# FEU2.net
KiCad netlist of a schematic drawn in EAGLE
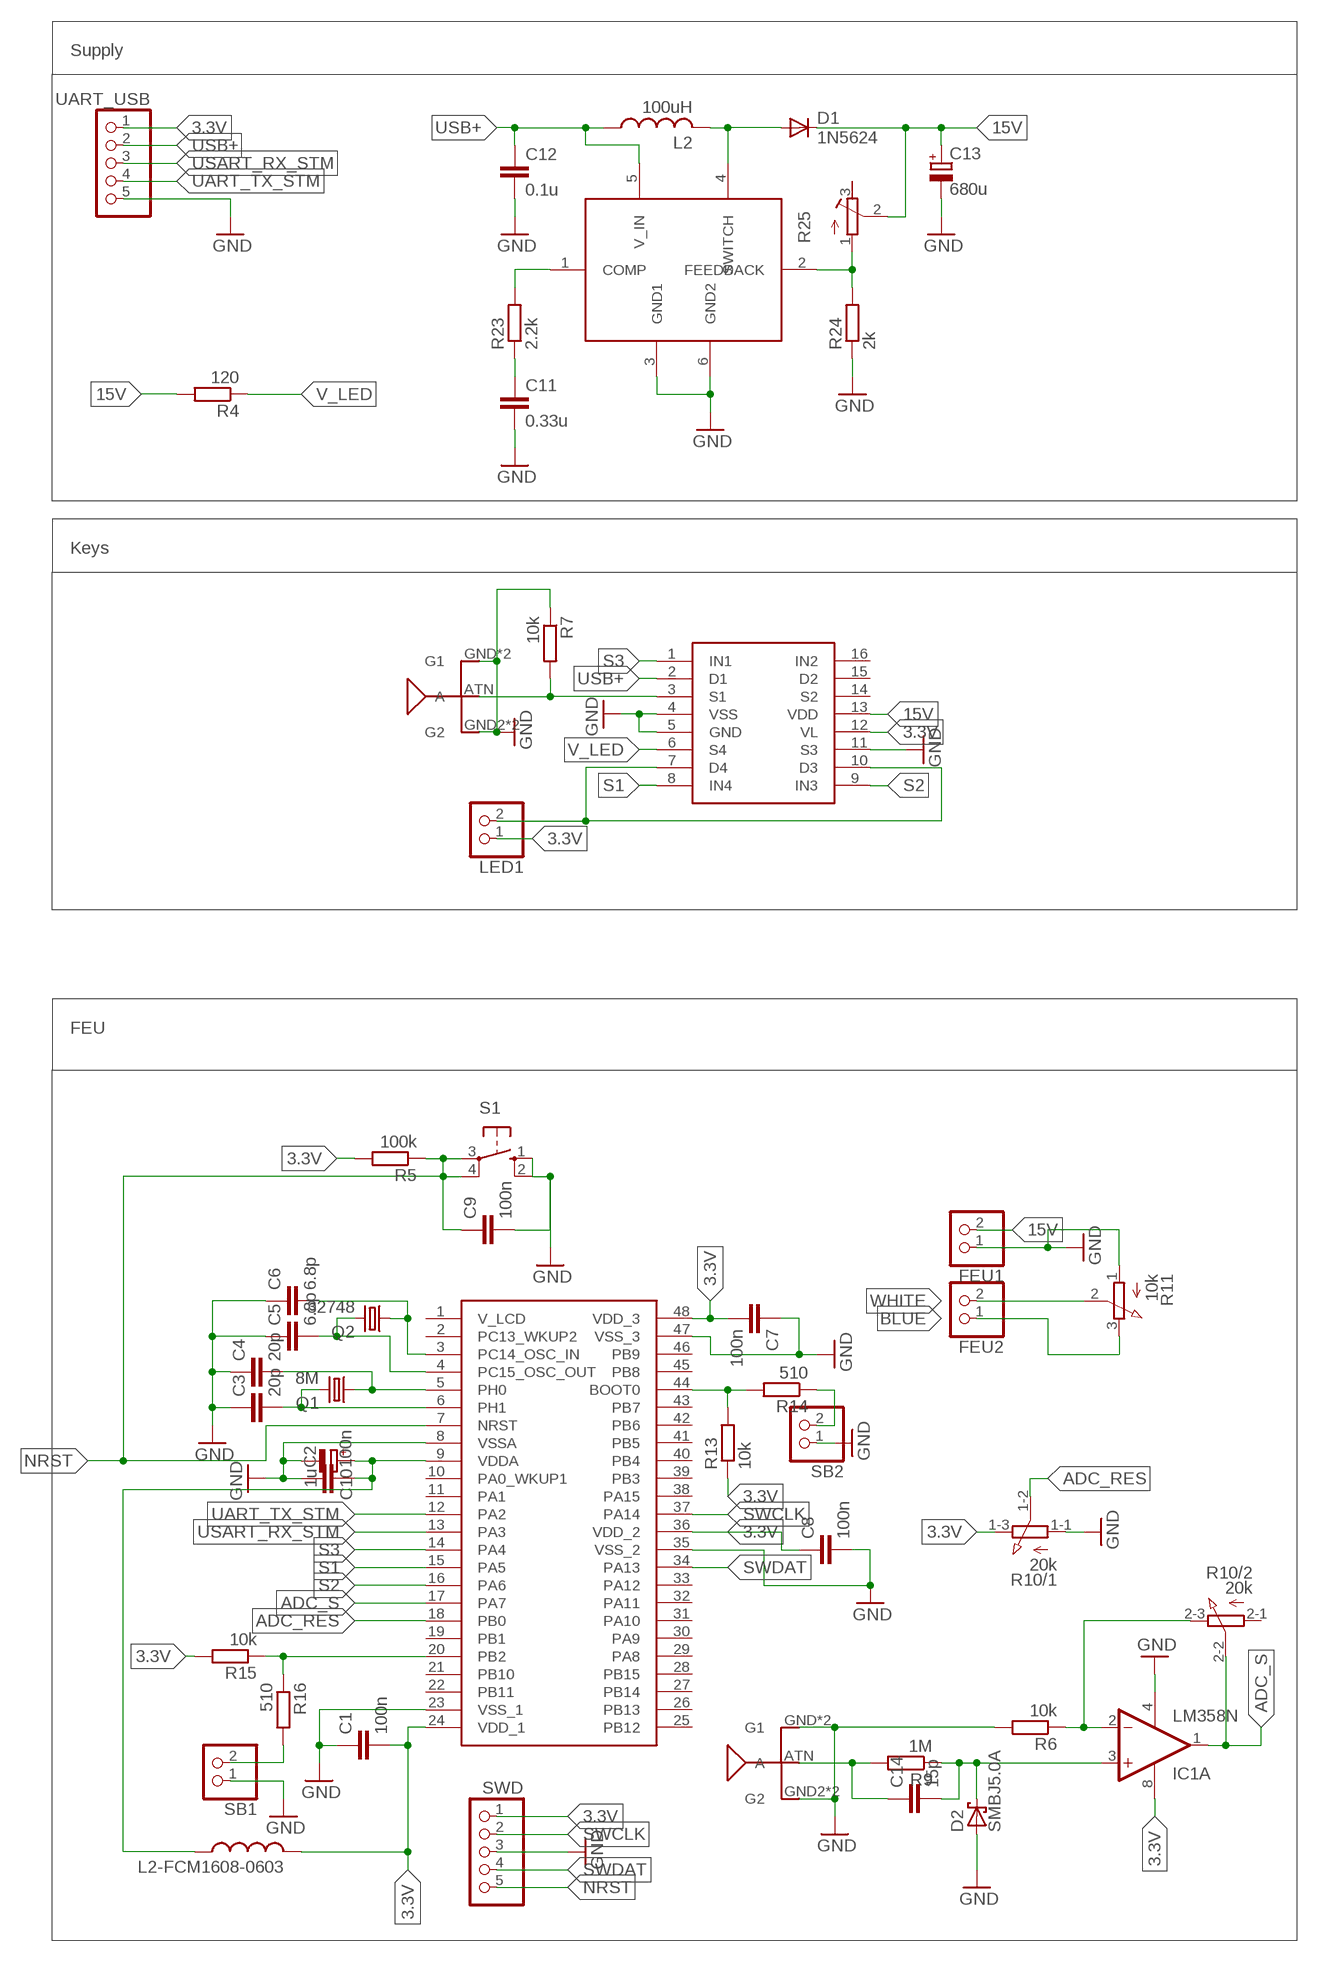
[diagram p0: schematic, sheet 1]

(export (version "E")
  (design (tool "Eeschema 10.0.6"))
  (components
    (comp (ref "C1")
      (value "100n")
      (footprint "eagle-import:C0805")
      (libsource (lib "eagle-import") (part "C-EUC0805"))
    )
    (comp (ref "C2")
      (value "100n")
      (footprint "eagle-import:C0805")
      (libsource (lib "eagle-import") (part "C-EUC0805"))
    )
    (comp (ref "C3")
      (value "20p")
      (footprint "eagle-import:C0805")
      (libsource (lib "eagle-import") (part "C-EUC0805"))
    )
    (comp (ref "C4")
      (value "20p")
      (footprint "eagle-import:C0805")
      (libsource (lib "eagle-import") (part "C-EUC0805"))
    )
    (comp (ref "C5")
      (value "6.8p")
      (footprint "eagle-import:C0805")
      (libsource (lib "eagle-import") (part "C-EUC0805"))
    )
    (comp (ref "C6")
      (value "6.8p")
      (footprint "eagle-import:C0805")
      (libsource (lib "eagle-import") (part "C-EUC0805"))
    )
    (comp (ref "C7")
      (value "100n")
      (footprint "eagle-import:C0805")
      (libsource (lib "eagle-import") (part "C-EUC0805"))
    )
    (comp (ref "C8")
      (value "100n")
      (footprint "eagle-import:C0805")
      (libsource (lib "eagle-import") (part "C-EUC0805"))
    )
    (comp (ref "C9")
      (value "100n")
      (footprint "eagle-import:C0805")
      (libsource (lib "eagle-import") (part "C-EUC0805"))
    )
    (comp (ref "C10")
      (value "1u")
      (footprint "eagle-import:A_3216-18W")
      (libsource (lib "eagle-import") (part "CPOL-EUA/3216-18W"))
    )
    (comp (ref "C11")
      (value "0.33u")
      (footprint "eagle-import:C0805")
      (libsource (lib "eagle-import") (part "C-EUC0805"))
    )
    (comp (ref "C12")
      (value "0.1u")
      (footprint "eagle-import:C0805")
      (libsource (lib "eagle-import") (part "C-EUC0805"))
    )
    (comp (ref "C13")
      (value "680u")
      (footprint "eagle-import:E5-5")
      (libsource (lib "eagle-import") (part "CPOL-EUE5-5"))
    )
    (comp (ref "C14")
      (value "15p")
      (footprint "eagle-import:C0805")
      (libsource (lib "eagle-import") (part "C-EUC0805"))
    )
    (comp (ref "D1")
      (value "1N5624")
      (footprint "eagle-import:DO201-15")
      (libsource (lib "eagle-import") (part "1N5624"))
    )
    (comp (ref "D2")
      (value "SMBJ5.0A")
      (footprint "eagle-import:C4111-15")
      (libsource (lib "eagle-import") (part "1N5908"))
    )
    (comp (ref "FEU1")
      (value "PINHD-1X2")
      (footprint "eagle-import:1X02")
      (libsource (lib "eagle-import") (part "PINHD-1X2"))
    )
    (comp (ref "FEU2")
      (value "PINHD-1X2")
      (footprint "eagle-import:1X02")
      (libsource (lib "eagle-import") (part "PINHD-1X2"))
    )
    (comp (ref "IC1")
      (value "LM358N")
      (footprint "eagle-import:DIL08")
      (libsource (lib "eagle-import") (part "LM358N"))
    )
    (comp (ref "L2")
      (value "100uH")
      (footprint "eagle-import:0207_5V")
      (libsource (lib "eagle-import") (part "L-US0207/5V"))
    )
    (comp (ref "L2-FCM1608-0603")
      (value "L-USL3216C")
      (footprint "eagle-import:L3216C")
      (libsource (lib "eagle-import") (part "L-USL3216C"))
    )
    (comp (ref "LED1")
      (value "PINHD-1X2")
      (footprint "eagle-import:1X02")
      (libsource (lib "eagle-import") (part "PINHD-1X2"))
    )
    (comp (ref "Q1")
      (value "8M")
      (footprint "eagle-import:HC49_S")
      (fields (field (name "OC_FARNELL") "1667008"))
      (libsource (lib "eagle-import") (part "CRYSTALHC49S"))
    )
    (comp (ref "Q2")
      (value "32748")
      (footprint "eagle-import:TC26H")
      (libsource (lib "eagle-import") (part "CRYSTALTC26H"))
    )
    (comp (ref "R4")
      (value "120")
      (footprint "eagle-import:R0805")
      (libsource (lib "eagle-import") (part "R-EU_R0805"))
    )
    (comp (ref "R5")
      (value "100k")
      (footprint "eagle-import:R0805")
      (libsource (lib "eagle-import") (part "R-EU_R0805"))
    )
    (comp (ref "R6")
      (value "10k")
      (footprint "eagle-import:M1206")
      (libsource (lib "eagle-import") (part "R-EU_M1206"))
    )
    (comp (ref "R7")
      (value "10k")
      (footprint "eagle-import:R0805")
      (libsource (lib "eagle-import") (part "R-EU_R0805"))
    )
    (comp (ref "R9")
      (value "1M")
      (footprint "eagle-import:M1206")
      (libsource (lib "eagle-import") (part "R-EU_M1206"))
    )
    (comp (ref "R10")
      (value "20k")
      (footprint "eagle-import:3RP_1610G")
      (libsource (lib "eagle-import") (part "3RP/1610G"))
    )
    (comp (ref "R11")
      (value "10k")
      (footprint "eagle-import:3RP_1610N")
      (libsource (lib "eagle-import") (part "3RP/1610N"))
    )
    (comp (ref "R13")
      (value "10k")
      (footprint "eagle-import:R0805")
      (libsource (lib "eagle-import") (part "R-EU_R0805"))
    )
    (comp (ref "R14")
      (value "510")
      (footprint "eagle-import:R0805")
      (libsource (lib "eagle-import") (part "R-EU_R0805"))
    )
    (comp (ref "R15")
      (value "10k")
      (footprint "eagle-import:R0805")
      (libsource (lib "eagle-import") (part "R-EU_R0805"))
    )
    (comp (ref "R16")
      (value "510")
      (footprint "eagle-import:R0805")
      (libsource (lib "eagle-import") (part "R-EU_R0805"))
    )
    (comp (ref "R23")
      (value "2.2k")
      (footprint "eagle-import:R0805")
      (libsource (lib "eagle-import") (part "R-EU_R0805"))
    )
    (comp (ref "R24")
      (value "2k")
      (footprint "eagle-import:R0805")
      (libsource (lib "eagle-import") (part "R-EU_R0805"))
    )
    (comp (ref "R25")
      (value "R-TRIMM3339P")
      (footprint "eagle-import:RTRIM3339P")
      (libsource (lib "eagle-import") (part "R-TRIMM3339P"))
    )
    (comp (ref "S1")
      (value "10-XX")
      (footprint "eagle-import:B3F-10XX")
      (fields (field (name "MPN") "B3F-1000"))
      (libsource (lib "eagle-import") (part "10-XX"))
    )
    (comp (ref "SB1")
      (value "PINHD-1X2")
      (footprint "eagle-import:1X02")
      (libsource (lib "eagle-import") (part "PINHD-1X2"))
    )
    (comp (ref "SB2")
      (value "PINHD-1X2")
      (footprint "eagle-import:1X02")
      (libsource (lib "eagle-import") (part "PINHD-1X2"))
    )
    (comp (ref "SWD")
      (value "PINHD-1X5")
      (footprint "eagle-import:1X05")
      (libsource (lib "eagle-import") (part "PINHD-1X5"))
    )
    (comp (ref "U$1")
      (value "STM32L152C6")
      (footprint "eagle-import:LQFP48")
      (libsource (lib "eagle-import") (part "STM32L152C6"))
    )
    (comp (ref "U$2")
      (value "GSM_ANT")
      (footprint "eagle-import:GSM")
      (libsource (lib "eagle-import") (part "GSM_ANT"))
    )
    (comp (ref "U$3")
      (value "GSM_ANT")
      (footprint "eagle-import:GSM")
      (libsource (lib "eagle-import") (part "GSM_ANT"))
    )
    (comp (ref "U$4")
      (value "LM2577")
      (footprint "eagle-import:TO263-5")
      (libsource (lib "eagle-import") (part "LM2577"))
    )
    (comp (ref "U$5")
      (value "ADG433BN")
      (footprint "eagle-import:DIL16")
      (libsource (lib "eagle-import") (part "ADG433BN"))
    )
    (comp (ref "UART_USB")
      (value "PINHD-1X5")
      (footprint "eagle-import:1X05")
      (libsource (lib "eagle-import") (part "PINHD-1X5"))
    )
  )
  (nets
    (net (code "1") (name "3.3V") (class "Default")
      (node (ref "C1") (pin "2") (pinfunction "2_2") (pintype "passive"))
      (node (ref "C7") (pin "2") (pinfunction "2_2") (pintype "passive"))
      (node (ref "C8") (pin "1") (pinfunction "1_1") (pintype "passive"))
      (node (ref "IC1") (pin "8") (pinfunction "V+_8") (pintype "power_in"))
      (node (ref "L2-FCM1608-0603") (pin "2") (pinfunction "2_2") (pintype "passive"))
      (node (ref "LED1") (pin "1") (pinfunction "1_1") (pintype "passive"))
      (node (ref "R10") (pin "1-3") (pinfunction "E_1-3") (pintype "passive"))
      (node (ref "R13") (pin "1") (pinfunction "1_1") (pintype "passive"))
      (node (ref "R15") (pin "2") (pinfunction "2_2") (pintype "passive"))
      (node (ref "R5") (pin "2") (pinfunction "2_2") (pintype "passive"))
      (node (ref "SWD") (pin "1") (pinfunction "1_1") (pintype "passive"))
      (node (ref "U$1") (pin "24") (pinfunction "VDD_1_24") (pintype "bidirectional"))
      (node (ref "U$1") (pin "36") (pinfunction "VDD_2_36") (pintype "bidirectional"))
      (node (ref "U$1") (pin "48") (pinfunction "VDD_3_48") (pintype "bidirectional"))
      (node (ref "U$5") (pin "12") (pinfunction "VL_12") (pintype "bidirectional"))
      (node (ref "UART_USB") (pin "1") (pinfunction "1_1") (pintype "passive"))
    )
    (net (code "2") (name "15V") (class "Default")
      (node (ref "C13") (pin "+") (pinfunction "+_+") (pintype "passive"))
      (node (ref "D1") (pin "C") (pinfunction "C_C") (pintype "passive"))
      (node (ref "FEU1") (pin "2") (pinfunction "2_2") (pintype "passive"))
      (node (ref "R25") (pin "2") (pinfunction "S_2") (pintype "passive"))
      (node (ref "R4") (pin "2") (pinfunction "2_2") (pintype "passive"))
      (node (ref "U$5") (pin "13") (pinfunction "VDD_13") (pintype "bidirectional"))
    )
    (net (code "3") (name "ADC_RES") (class "Default")
      (node (ref "R10") (pin "1-2") (pinfunction "S_1-2") (pintype "passive"))
      (node (ref "U$1") (pin "18") (pinfunction "PB0_18") (pintype "bidirectional"))
    )
    (net (code "4") (name "ADC_S") (class "Default")
      (node (ref "IC1") (pin "1") (pinfunction "OUT_1") (pintype "output"))
      (node (ref "R10") (pin "2-2") (pinfunction "S_2-2") (pintype "passive"))
      (node (ref "U$1") (pin "17") (pinfunction "PA7_17") (pintype "bidirectional"))
    )
    (net (code "5") (name "BLUE") (class "Default")
      (node (ref "FEU2") (pin "1") (pinfunction "1_1") (pintype "passive"))
      (node (ref "R11") (pin "3") (pinfunction "E_3") (pintype "passive"))
    )
    (net (code "6") (name "GND") (class "Default")
      (node (ref "C1") (pin "1") (pinfunction "1_1") (pintype "passive"))
      (node (ref "C10") (pin "-") (pinfunction "-_-") (pintype "passive"))
      (node (ref "C11") (pin "2") (pinfunction "2_2") (pintype "passive"))
      (node (ref "C12") (pin "2") (pinfunction "2_2") (pintype "passive"))
      (node (ref "C13") (pin "-") (pinfunction "-_-") (pintype "passive"))
      (node (ref "C2") (pin "1") (pinfunction "1_1") (pintype "passive"))
      (node (ref "C3") (pin "1") (pinfunction "1_1") (pintype "passive"))
      (node (ref "C4") (pin "1") (pinfunction "1_1") (pintype "passive"))
      (node (ref "C5") (pin "1") (pinfunction "1_1") (pintype "passive"))
      (node (ref "C6") (pin "1") (pinfunction "1_1") (pintype "passive"))
      (node (ref "C7") (pin "1") (pinfunction "1_1") (pintype "passive"))
      (node (ref "C8") (pin "2") (pinfunction "2_2") (pintype "passive"))
      (node (ref "C9") (pin "2") (pinfunction "2_2") (pintype "passive"))
      (node (ref "D2") (pin "A") (pinfunction "A_A") (pintype "passive"))
      (node (ref "FEU1") (pin "1") (pinfunction "1_1") (pintype "passive"))
      (node (ref "IC1") (pin "4") (pinfunction "V-_4") (pintype "power_in"))
      (node (ref "R10") (pin "1-1") (pinfunction "A_1-1") (pintype "passive"))
      (node (ref "R11") (pin "1") (pinfunction "A_1") (pintype "passive"))
      (node (ref "R24") (pin "1") (pinfunction "1_1") (pintype "passive"))
      (node (ref "R6") (pin "2") (pinfunction "2_2") (pintype "passive"))
      (node (ref "R7") (pin "1") (pinfunction "1_1") (pintype "passive"))
      (node (ref "S1") (pin "1") (pinfunction "S_1") (pintype "passive"))
      (node (ref "S1") (pin "2") (pinfunction "S1_2") (pintype "passive"))
      (node (ref "SB1") (pin "1") (pinfunction "1_1") (pintype "passive"))
      (node (ref "SB2") (pin "1") (pinfunction "1_1") (pintype "passive"))
      (node (ref "SWD") (pin "3") (pinfunction "3_3") (pintype "passive"))
      (node (ref "U$1") (pin "23") (pinfunction "VSS_1_23") (pintype "bidirectional"))
      (node (ref "U$1") (pin "35") (pinfunction "VSS_2_35") (pintype "bidirectional"))
      (node (ref "U$1") (pin "47") (pinfunction "VSS_3_47") (pintype "bidirectional"))
      (node (ref "U$1") (pin "8") (pinfunction "VSSA_8") (pintype "bidirectional"))
      (node (ref "U$2") (pin "GND") (pinfunction "G1_GND") (pintype "bidirectional"))
      (node (ref "U$2") (pin "GND1") (pinfunction "G1_GND1") (pintype "bidirectional"))
      (node (ref "U$2") (pin "GND2") (pinfunction "G2_GND2") (pintype "bidirectional"))
      (node (ref "U$2") (pin "GND3") (pinfunction "G2_GND3") (pintype "bidirectional"))
      (node (ref "U$3") (pin "GND") (pinfunction "G1_GND") (pintype "bidirectional"))
      (node (ref "U$3") (pin "GND1") (pinfunction "G1_GND1") (pintype "bidirectional"))
      (node (ref "U$3") (pin "GND2") (pinfunction "G2_GND2") (pintype "bidirectional"))
      (node (ref "U$3") (pin "GND3") (pinfunction "G2_GND3") (pintype "bidirectional"))
      (node (ref "U$4") (pin "3") (pinfunction "GND1_3") (pintype "bidirectional"))
      (node (ref "U$4") (pin "6") (pinfunction "GND2_6") (pintype "bidirectional"))
      (node (ref "U$5") (pin "11") (pinfunction "S3_11") (pintype "bidirectional"))
      (node (ref "U$5") (pin "4") (pinfunction "VSS_4") (pintype "bidirectional"))
      (node (ref "U$5") (pin "5") (pinfunction "GND_5") (pintype "bidirectional"))
      (node (ref "UART_USB") (pin "5") (pinfunction "5_5") (pintype "passive"))
    )
    (net (code "7") (name "NRST") (class "Default")
      (node (ref "C9") (pin "1") (pinfunction "1_1") (pintype "passive"))
      (node (ref "R5") (pin "1") (pinfunction "1_1") (pintype "passive"))
      (node (ref "S1") (pin "3") (pinfunction "P_3") (pintype "passive"))
      (node (ref "S1") (pin "4") (pinfunction "P1_4") (pintype "passive"))
      (node (ref "SWD") (pin "5") (pinfunction "5_5") (pintype "passive"))
      (node (ref "U$1") (pin "7") (pinfunction "NRST_7") (pintype "bidirectional"))
    )
    (net (code "8") (name "Net-(C11-Pad1)") (class "Default")
      (node (ref "C11") (pin "1") (pinfunction "1_1") (pintype "passive"))
      (node (ref "R23") (pin "1") (pinfunction "1_1") (pintype "passive"))
    )
    (net (code "9") (name "Net-(IC1A-+IN)") (class "Default")
      (node (ref "C14") (pin "2") (pinfunction "2_2") (pintype "passive"))
      (node (ref "D2") (pin "C") (pinfunction "C_C") (pintype "passive"))
      (node (ref "IC1") (pin "3") (pinfunction "+IN_3") (pintype "input"))
      (node (ref "R9") (pin "1") (pinfunction "1_1") (pintype "passive"))
    )
    (net (code "10") (name "Net-(IC1A--IN)") (class "Default")
      (node (ref "IC1") (pin "2") (pinfunction "-IN_2") (pintype "input"))
      (node (ref "R10") (pin "2-3") (pinfunction "E_2-3") (pintype "passive"))
      (node (ref "R6") (pin "1") (pinfunction "1_1") (pintype "passive"))
    )
    (net (code "11") (name "Net-(R14-Pad1)") (class "Default")
      (node (ref "R14") (pin "1") (pinfunction "1_1") (pintype "passive"))
      (node (ref "SB2") (pin "2") (pinfunction "2_2") (pintype "passive"))
    )
    (net (code "12") (name "Net-(R16-Pad2)") (class "Default")
      (node (ref "R16") (pin "2") (pinfunction "2_2") (pintype "passive"))
      (node (ref "SB1") (pin "2") (pinfunction "2_2") (pintype "passive"))
    )
    (net (code "13") (name "Net-(R25-E)") (class "Default")
      (node (ref "R24") (pin "2") (pinfunction "2_2") (pintype "passive"))
      (node (ref "R25") (pin "1") (pinfunction "E_1") (pintype "passive"))
      (node (ref "U$4") (pin "2") (pinfunction "FEEDBACK_2") (pintype "bidirectional"))
    )
    (net (code "14") (name "Net-(U$1-BOOT0)") (class "Default")
      (node (ref "R13") (pin "2") (pinfunction "2_2") (pintype "passive"))
      (node (ref "R14") (pin "2") (pinfunction "2_2") (pintype "passive"))
      (node (ref "U$1") (pin "44") (pinfunction "BOOT0_44") (pintype "bidirectional"))
    )
    (net (code "15") (name "Net-(U$1-PB2)") (class "Default")
      (node (ref "R15") (pin "1") (pinfunction "1_1") (pintype "passive"))
      (node (ref "R16") (pin "1") (pinfunction "1_1") (pintype "passive"))
      (node (ref "U$1") (pin "20") (pinfunction "PB2_20") (pintype "bidirectional"))
    )
    (net (code "16") (name "Net-(U$1-PC14_OSC_IN)") (class "Default")
      (node (ref "C6") (pin "2") (pinfunction "2_2") (pintype "passive"))
      (node (ref "Q2") (pin "1") (pinfunction "1_1") (pintype "passive"))
      (node (ref "U$1") (pin "3") (pinfunction "PC14_OSC_IN_3") (pintype "bidirectional"))
    )
    (net (code "17") (name "Net-(U$1-PC15_OSC_OUT)") (class "Default")
      (node (ref "C5") (pin "2") (pinfunction "2_2") (pintype "passive"))
      (node (ref "Q2") (pin "2") (pinfunction "2_2") (pintype "passive"))
      (node (ref "U$1") (pin "4") (pinfunction "PC15_OSC_OUT_4") (pintype "bidirectional"))
    )
    (net (code "18") (name "Net-(U$1-PH0)") (class "Default")
      (node (ref "C4") (pin "2") (pinfunction "2_2") (pintype "passive"))
      (node (ref "Q1") (pin "1") (pinfunction "1_1") (pintype "passive"))
      (node (ref "U$1") (pin "5") (pinfunction "PH0_5") (pintype "bidirectional"))
    )
    (net (code "19") (name "Net-(U$1-PH1)") (class "Default")
      (node (ref "C3") (pin "2") (pinfunction "2_2") (pintype "passive"))
      (node (ref "Q1") (pin "2") (pinfunction "2_2") (pintype "passive"))
      (node (ref "U$1") (pin "6") (pinfunction "PH1_6") (pintype "bidirectional"))
    )
    (net (code "20") (name "Net-(U$1-VDDA)") (class "Default")
      (node (ref "C10") (pin "+") (pinfunction "+_+") (pintype "passive"))
      (node (ref "C2") (pin "2") (pinfunction "2_2") (pintype "passive"))
      (node (ref "L2-FCM1608-0603") (pin "1") (pinfunction "1_1") (pintype "passive"))
      (node (ref "U$1") (pin "9") (pinfunction "VDDA_9") (pintype "bidirectional"))
    )
    (net (code "21") (name "Net-(U$2-A)") (class "Default")
      (node (ref "C14") (pin "1") (pinfunction "1_1") (pintype "passive"))
      (node (ref "R9") (pin "2") (pinfunction "2_2") (pintype "passive"))
      (node (ref "U$2") (pin "ATN") (pinfunction "A_ATN") (pintype "bidirectional"))
    )
    (net (code "22") (name "Net-(U$3-A)") (class "Default")
      (node (ref "R7") (pin "2") (pinfunction "2_2") (pintype "passive"))
      (node (ref "U$3") (pin "ATN") (pinfunction "A_ATN") (pintype "bidirectional"))
      (node (ref "U$5") (pin "3") (pinfunction "S1_3") (pintype "bidirectional"))
    )
    (net (code "23") (name "Net-(U$4-COMP)") (class "Default")
      (node (ref "R23") (pin "2") (pinfunction "2_2") (pintype "passive"))
      (node (ref "U$4") (pin "1") (pinfunction "COMP_1") (pintype "bidirectional"))
    )
    (net (code "24") (name "Net-(U$4-SWITCH)") (class "Default")
      (node (ref "D1") (pin "A") (pinfunction "A_A") (pintype "passive"))
      (node (ref "L2") (pin "2") (pinfunction "2_2") (pintype "passive"))
      (node (ref "U$4") (pin "4") (pinfunction "SWITCH_4") (pintype "bidirectional"))
    )
    (net (code "25") (name "Net-(U$5-D3)") (class "Default")
      (node (ref "LED1") (pin "2") (pinfunction "2_2") (pintype "passive"))
      (node (ref "U$5") (pin "10") (pinfunction "D3_10") (pintype "bidirectional"))
      (node (ref "U$5") (pin "7") (pinfunction "D4_7") (pintype "bidirectional"))
    )
    (net (code "26") (name "S1") (class "Default")
      (node (ref "U$1") (pin "15") (pinfunction "PA5_15") (pintype "bidirectional"))
      (node (ref "U$5") (pin "8") (pinfunction "IN4_8") (pintype "bidirectional"))
    )
    (net (code "27") (name "S2") (class "Default")
      (node (ref "U$1") (pin "16") (pinfunction "PA6_16") (pintype "bidirectional"))
      (node (ref "U$5") (pin "9") (pinfunction "IN3_9") (pintype "bidirectional"))
    )
    (net (code "28") (name "S3") (class "Default")
      (node (ref "U$1") (pin "14") (pinfunction "PA4_14") (pintype "bidirectional"))
      (node (ref "U$5") (pin "1") (pinfunction "IN1_1") (pintype "bidirectional"))
    )
    (net (code "29") (name "SWCLK") (class "Default")
      (node (ref "SWD") (pin "2") (pinfunction "2_2") (pintype "passive"))
      (node (ref "U$1") (pin "37") (pinfunction "PA14_37") (pintype "bidirectional"))
    )
    (net (code "30") (name "SWDAT") (class "Default")
      (node (ref "SWD") (pin "4") (pinfunction "4_4") (pintype "passive"))
      (node (ref "U$1") (pin "34") (pinfunction "PA13_34") (pintype "bidirectional"))
    )
    (net (code "31") (name "UART_TX_STM") (class "Default")
      (node (ref "U$1") (pin "12") (pinfunction "PA2_12") (pintype "bidirectional"))
      (node (ref "UART_USB") (pin "4") (pinfunction "4_4") (pintype "passive"))
    )
    (net (code "32") (name "USART_RX_STM") (class "Default")
      (node (ref "U$1") (pin "13") (pinfunction "PA3_13") (pintype "bidirectional"))
      (node (ref "UART_USB") (pin "3") (pinfunction "3_3") (pintype "passive"))
    )
    (net (code "33") (name "USB+") (class "Default")
      (node (ref "C12") (pin "1") (pinfunction "1_1") (pintype "passive"))
      (node (ref "L2") (pin "1") (pinfunction "1_1") (pintype "passive"))
      (node (ref "U$4") (pin "5") (pinfunction "V_IN_5") (pintype "bidirectional"))
      (node (ref "U$5") (pin "2") (pinfunction "D1_2") (pintype "bidirectional"))
      (node (ref "UART_USB") (pin "2") (pinfunction "2_2") (pintype "passive"))
    )
    (net (code "34") (name "V_LED") (class "Default")
      (node (ref "R4") (pin "1") (pinfunction "1_1") (pintype "passive"))
      (node (ref "U$5") (pin "6") (pinfunction "S4_6") (pintype "bidirectional"))
    )
    (net (code "35") (name "WHITE") (class "Default")
      (node (ref "FEU2") (pin "2") (pinfunction "2_2") (pintype "passive"))
      (node (ref "R11") (pin "2") (pinfunction "S_2") (pintype "passive"))
    )
    (net (code "36") (name "unconnected-(R10B-A-Pad2-1)") (class "Default")
      (node (ref "R10") (pin "2-1") (pinfunction "A_2-1") (pintype "passive"))
    )
    (net (code "37") (name "unconnected-(R25-A-Pad3)") (class "Default")
      (node (ref "R25") (pin "3") (pinfunction "A_3") (pintype "passive"))
    )
    (net (code "38") (name "unconnected-(U$1-PA0_WKUP1-Pad10)") (class "Default")
      (node (ref "U$1") (pin "10") (pinfunction "PA0_WKUP1_10") (pintype "bidirectional"))
    )
    (net (code "39") (name "unconnected-(U$1-PA1-Pad11)") (class "Default")
      (node (ref "U$1") (pin "11") (pinfunction "PA1_11") (pintype "bidirectional"))
    )
    (net (code "40") (name "unconnected-(U$1-PA8-Pad29)") (class "Default")
      (node (ref "U$1") (pin "29") (pinfunction "PA8_29") (pintype "bidirectional"))
    )
    (net (code "41") (name "unconnected-(U$1-PA9-Pad30)") (class "Default")
      (node (ref "U$1") (pin "30") (pinfunction "PA9_30") (pintype "bidirectional"))
    )
    (net (code "42") (name "unconnected-(U$1-PA10-Pad31)") (class "Default")
      (node (ref "U$1") (pin "31") (pinfunction "PA10_31") (pintype "bidirectional"))
    )
    (net (code "43") (name "unconnected-(U$1-PA11-Pad32)") (class "Default")
      (node (ref "U$1") (pin "32") (pinfunction "PA11_32") (pintype "bidirectional"))
    )
    (net (code "44") (name "unconnected-(U$1-PA12-Pad33)") (class "Default")
      (node (ref "U$1") (pin "33") (pinfunction "PA12_33") (pintype "bidirectional"))
    )
    (net (code "45") (name "unconnected-(U$1-PA15-Pad38)") (class "Default")
      (node (ref "U$1") (pin "38") (pinfunction "PA15_38") (pintype "bidirectional"))
    )
    (net (code "46") (name "unconnected-(U$1-PB1-Pad19)") (class "Default")
      (node (ref "U$1") (pin "19") (pinfunction "PB1_19") (pintype "bidirectional"))
    )
    (net (code "47") (name "unconnected-(U$1-PB3-Pad39)") (class "Default")
      (node (ref "U$1") (pin "39") (pinfunction "PB3_39") (pintype "bidirectional"))
    )
    (net (code "48") (name "unconnected-(U$1-PB4-Pad40)") (class "Default")
      (node (ref "U$1") (pin "40") (pinfunction "PB4_40") (pintype "bidirectional"))
    )
    (net (code "49") (name "unconnected-(U$1-PB5-Pad41)") (class "Default")
      (node (ref "U$1") (pin "41") (pinfunction "PB5_41") (pintype "bidirectional"))
    )
    (net (code "50") (name "unconnected-(U$1-PB6-Pad42)") (class "Default")
      (node (ref "U$1") (pin "42") (pinfunction "PB6_42") (pintype "bidirectional"))
    )
    (net (code "51") (name "unconnected-(U$1-PB7-Pad43)") (class "Default")
      (node (ref "U$1") (pin "43") (pinfunction "PB7_43") (pintype "bidirectional"))
    )
    (net (code "52") (name "unconnected-(U$1-PB8-Pad45)") (class "Default")
      (node (ref "U$1") (pin "45") (pinfunction "PB8_45") (pintype "bidirectional"))
    )
    (net (code "53") (name "unconnected-(U$1-PB9-Pad46)") (class "Default")
      (node (ref "U$1") (pin "46") (pinfunction "PB9_46") (pintype "bidirectional"))
    )
    (net (code "54") (name "unconnected-(U$1-PB10-Pad21)") (class "Default")
      (node (ref "U$1") (pin "21") (pinfunction "PB10_21") (pintype "bidirectional"))
    )
    (net (code "55") (name "unconnected-(U$1-PB11-Pad22)") (class "Default")
      (node (ref "U$1") (pin "22") (pinfunction "PB11_22") (pintype "bidirectional"))
    )
    (net (code "56") (name "unconnected-(U$1-PB12-Pad25)") (class "Default")
      (node (ref "U$1") (pin "25") (pinfunction "PB12_25") (pintype "bidirectional"))
    )
    (net (code "57") (name "unconnected-(U$1-PB13-Pad26)") (class "Default")
      (node (ref "U$1") (pin "26") (pinfunction "PB13_26") (pintype "bidirectional"))
    )
    (net (code "58") (name "unconnected-(U$1-PB14-Pad27)") (class "Default")
      (node (ref "U$1") (pin "27") (pinfunction "PB14_27") (pintype "bidirectional"))
    )
    (net (code "59") (name "unconnected-(U$1-PB15-Pad28)") (class "Default")
      (node (ref "U$1") (pin "28") (pinfunction "PB15_28") (pintype "bidirectional"))
    )
    (net (code "60") (name "unconnected-(U$1-PC13_WKUP2-Pad2)") (class "Default")
      (node (ref "U$1") (pin "2") (pinfunction "PC13_WKUP2_2") (pintype "bidirectional"))
    )
    (net (code "61") (name "unconnected-(U$1-V_LCD-Pad1)") (class "Default")
      (node (ref "U$1") (pin "1") (pinfunction "V_LCD_1") (pintype "bidirectional"))
    )
    (net (code "62") (name "unconnected-(U$5-D2-Pad15)") (class "Default")
      (node (ref "U$5") (pin "15") (pinfunction "D2_15") (pintype "bidirectional"))
    )
    (net (code "63") (name "unconnected-(U$5-IN2-Pad16)") (class "Default")
      (node (ref "U$5") (pin "16") (pinfunction "IN2_16") (pintype "bidirectional"))
    )
    (net (code "64") (name "unconnected-(U$5-S2-Pad14)") (class "Default")
      (node (ref "U$5") (pin "14") (pinfunction "S2_14") (pintype "bidirectional"))
    )
  )
)
